# etch-a-sketch.net
KiCad netlist of a schematic drawn in EAGLE
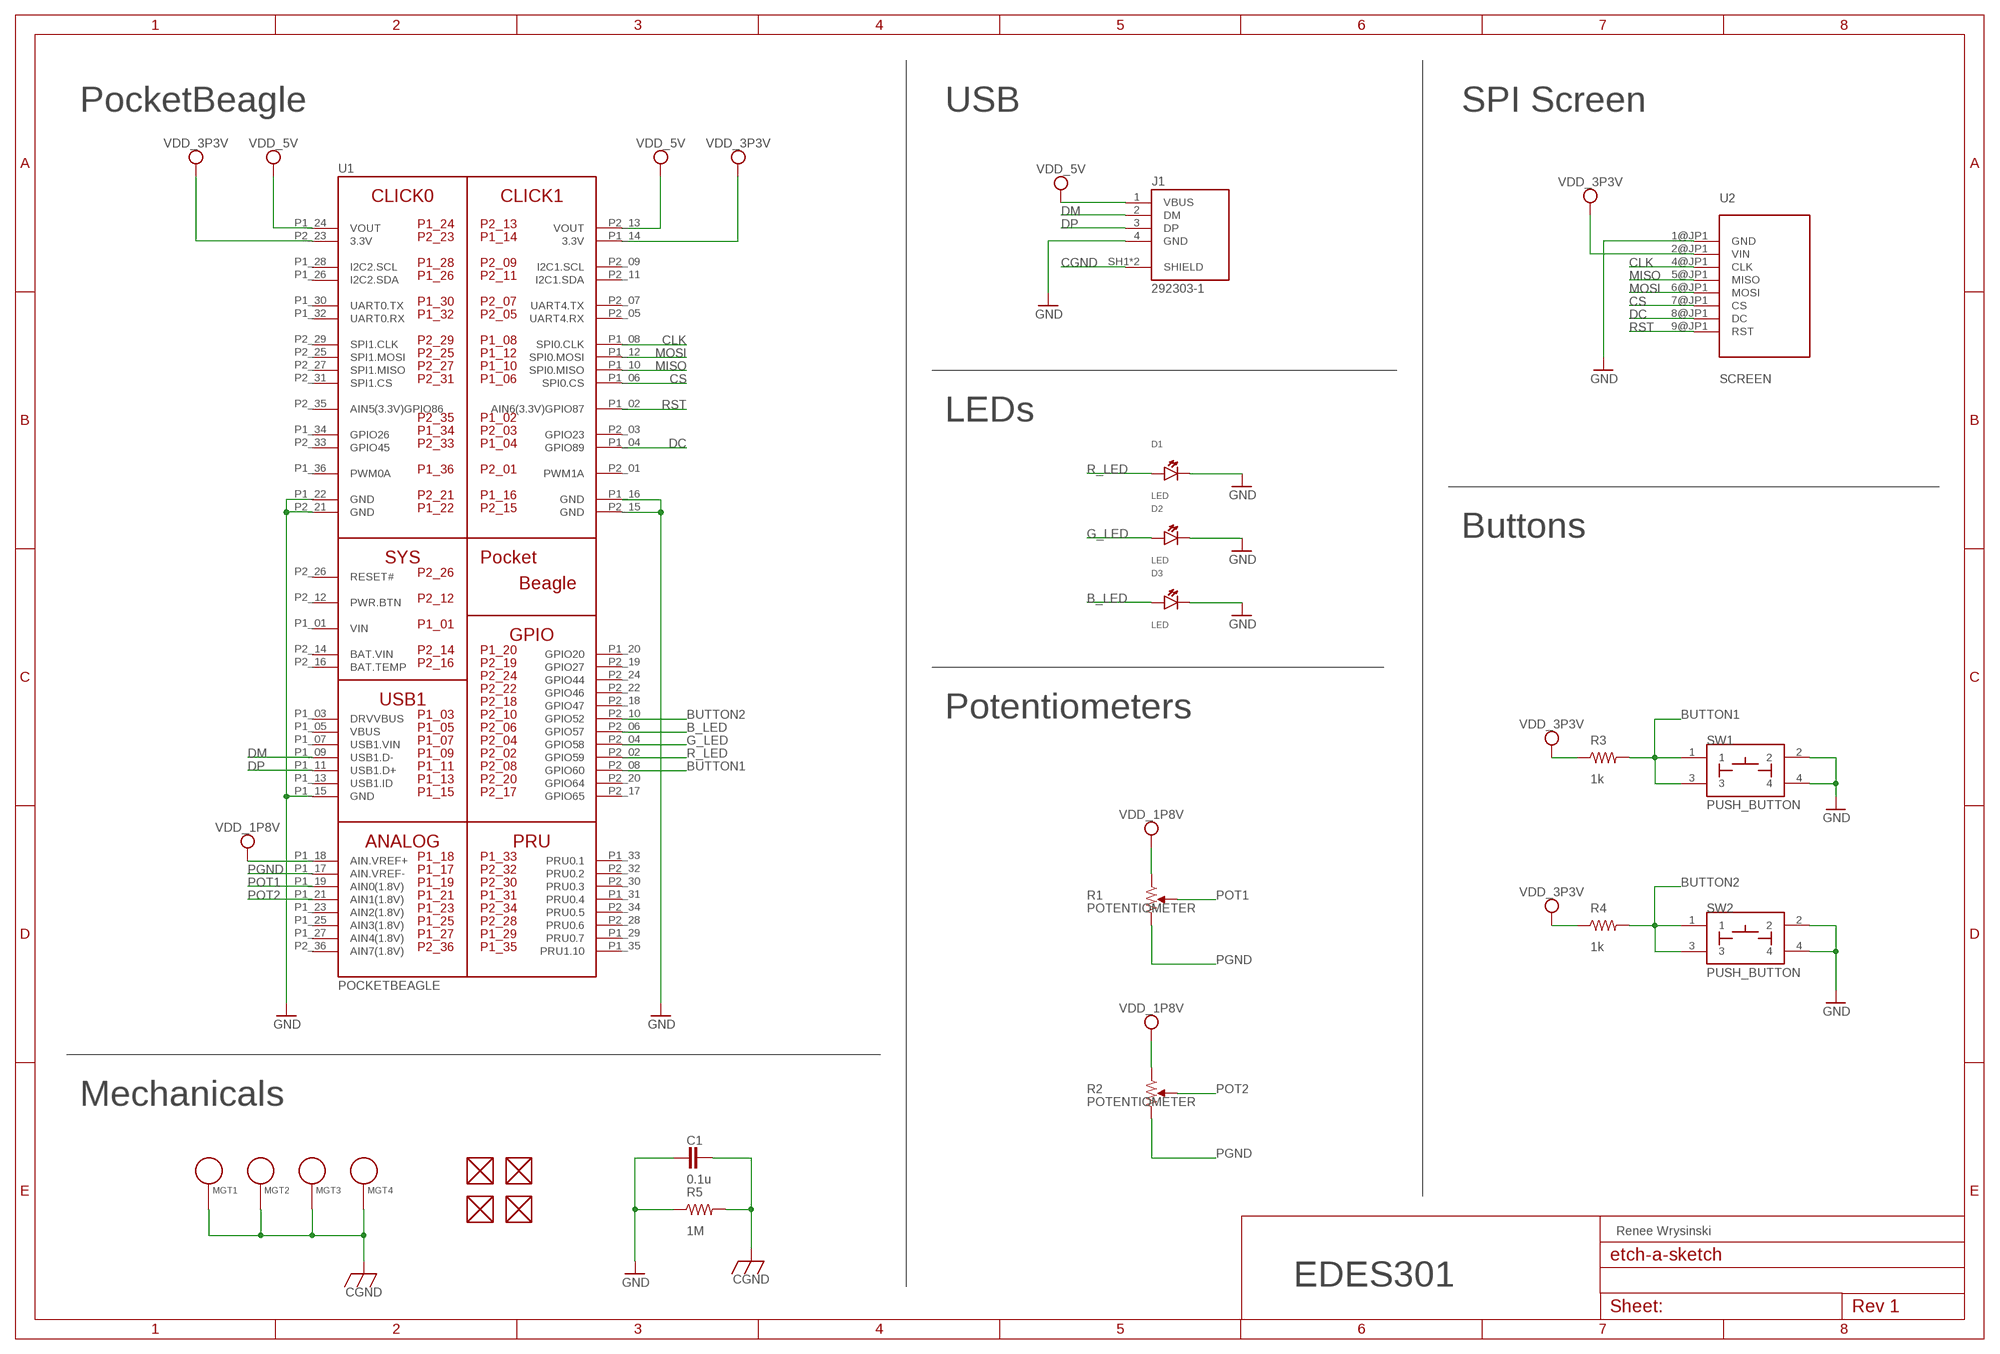
[diagram p0: schematic, sheet 1]

(export (version "E")
  (design (tool "Eeschema 10.0.6"))
  (components
    (comp (ref "C1")
      (value "0.1u")
      (footprint "eagle-import:C0603")
      (libsource (lib "eagle-import") (part "C_C0603"))
    )
    (comp (ref "D1")
      (value "LED")
      (footprint "eagle-import:EIA-STD")
      (libsource (lib "eagle-import") (part "LED"))
    )
    (comp (ref "D2")
      (value "LED")
      (footprint "eagle-import:EIA-STD")
      (libsource (lib "eagle-import") (part "LED"))
    )
    (comp (ref "D3")
      (value "LED")
      (footprint "eagle-import:EIA-STD")
      (libsource (lib "eagle-import") (part "LED"))
    )
    (comp (ref "FUD1")
      (value "FIDUCIAL")
      (footprint "eagle-import:FIDUCIAL_40MIL")
      (libsource (lib "eagle-import") (part "FIDUCIAL"))
    )
    (comp (ref "FUD2")
      (value "FIDUCIAL")
      (footprint "eagle-import:FIDUCIAL_40MIL")
      (libsource (lib "eagle-import") (part "FIDUCIAL"))
    )
    (comp (ref "FUD3")
      (value "FIDUCIAL")
      (footprint "eagle-import:FIDUCIAL_40MIL")
      (libsource (lib "eagle-import") (part "FIDUCIAL"))
    )
    (comp (ref "FUD4")
      (value "FIDUCIAL")
      (footprint "eagle-import:FIDUCIAL_40MIL")
      (libsource (lib "eagle-import") (part "FIDUCIAL"))
    )
    (comp (ref "J1")
      (value "292303-1")
      (footprint "eagle-import:TE_292303-1")
      (fields (field (name "MF") "TE Connectivity"))
      (libsource (lib "eagle-import") (part "292303-1"))
    )
    (comp (ref "MGT1")
      (value "MOUNTING_HOLE")
      (footprint "eagle-import:MOUNTING_HOLE")
      (libsource (lib "eagle-import") (part "MOUNTING_HOLE"))
    )
    (comp (ref "MGT2")
      (value "MOUNTING_HOLE")
      (footprint "eagle-import:MOUNTING_HOLE")
      (libsource (lib "eagle-import") (part "MOUNTING_HOLE"))
    )
    (comp (ref "MGT3")
      (value "MOUNTING_HOLE")
      (footprint "eagle-import:MOUNTING_HOLE")
      (libsource (lib "eagle-import") (part "MOUNTING_HOLE"))
    )
    (comp (ref "MGT4")
      (value "MOUNTING_HOLE")
      (footprint "eagle-import:MOUNTING_HOLE")
      (libsource (lib "eagle-import") (part "MOUNTING_HOLE"))
    )
    (comp (ref "R1")
      (value "POTENTIOMETER")
      (footprint "eagle-import:POT-PO90S")
      (libsource (lib "eagle-import") (part "POTENTIOMETER"))
    )
    (comp (ref "R2")
      (value "POTENTIOMETER")
      (footprint "eagle-import:POT-PO90S")
      (libsource (lib "eagle-import") (part "POTENTIOMETER"))
    )
    (comp (ref "R3")
      (value "1k")
      (footprint "eagle-import:R0603")
      (libsource (lib "eagle-import") (part "R_R0603"))
    )
    (comp (ref "R4")
      (value "1k")
      (footprint "eagle-import:R0603")
      (libsource (lib "eagle-import") (part "R_R0603"))
    )
    (comp (ref "R5")
      (value "1M")
      (footprint "eagle-import:R0603")
      (libsource (lib "eagle-import") (part "R_R0603"))
    )
    (comp (ref "SW1")
      (value "PUSH_BUTTON")
      (footprint "eagle-import:BUTTON_12.5MM")
      (libsource (lib "eagle-import") (part "PUSH_BUTTON"))
    )
    (comp (ref "SW2")
      (value "PUSH_BUTTON")
      (footprint "eagle-import:BUTTON_12.5MM")
      (libsource (lib "eagle-import") (part "PUSH_BUTTON"))
    )
    (comp (ref "U1")
      (value "POCKETBEAGLE")
      (footprint "eagle-import:POCKETBEAGLE")
      (libsource (lib "eagle-import") (part "POCKETBEAGLE"))
    )
    (comp (ref "U2")
      (value "SCREEN")
      (footprint "eagle-import:ADAFRUIT_2.8_TFT_BREAKOUT_V2")
      (libsource (lib "eagle-import") (part "ADAFRUIT_2.8_TFT_BREAKOUT_V2"))
    )
  )
  (nets
    (net (code "1") (name "/BAT.VIN") (class "Default")
      (node (ref "U1") (pin "P2_14") (pinfunction "BAT.VIN_P2_14") (pintype "power_in"))
    )
    (net (code "2") (name "/BUTTON1") (class "Default")
      (node (ref "R3") (pin "2") (pinfunction "2_2") (pintype "passive"))
      (node (ref "SW1") (pin "1") (pinfunction "1_1") (pintype "bidirectional"))
      (node (ref "SW1") (pin "3") (pinfunction "3_3") (pintype "bidirectional"))
      (node (ref "U1") (pin "P2_08") (pinfunction "GPIO60_P2_08") (pintype "bidirectional"))
    )
    (net (code "3") (name "/BUTTON2") (class "Default")
      (node (ref "R4") (pin "2") (pinfunction "2_2") (pintype "passive"))
      (node (ref "SW2") (pin "1") (pinfunction "1_1") (pintype "bidirectional"))
      (node (ref "SW2") (pin "3") (pinfunction "3_3") (pintype "bidirectional"))
      (node (ref "U1") (pin "P2_10") (pinfunction "GPIO52_P2_10") (pintype "bidirectional"))
    )
    (net (code "4") (name "/B_LED") (class "Default")
      (node (ref "D3") (pin "ANODE") (pinfunction "ANODE_ANODE") (pintype "bidirectional"))
      (node (ref "U1") (pin "P2_06") (pinfunction "GPIO57_P2_06") (pintype "bidirectional"))
    )
    (net (code "5") (name "/CLK") (class "Default")
      (node (ref "U1") (pin "P1_08") (pinfunction "SPI0.CLK_P1_08") (pintype "bidirectional"))
      (node (ref "U2") (pin "4@JP1") (pinfunction "CLK_4@JP1") (pintype "bidirectional"))
    )
    (net (code "6") (name "/CS") (class "Default")
      (node (ref "U1") (pin "P1_06") (pinfunction "SPI0.CS_P1_06") (pintype "bidirectional"))
      (node (ref "U2") (pin "7@JP1") (pinfunction "CS_7@JP1") (pintype "bidirectional"))
    )
    (net (code "7") (name "/DC") (class "Default")
      (node (ref "U1") (pin "P1_04") (pinfunction "GPIO89_P1_04") (pintype "bidirectional"))
      (node (ref "U2") (pin "8@JP1") (pinfunction "DC_8@JP1") (pintype "bidirectional"))
    )
    (net (code "8") (name "/DM") (class "Default")
      (node (ref "J1") (pin "2") (pinfunction "DM_2") (pintype "passive"))
      (node (ref "U1") (pin "P1_09") (pinfunction "USB1.D-_P1_09") (pintype "bidirectional"))
    )
    (net (code "9") (name "/DP") (class "Default")
      (node (ref "J1") (pin "3") (pinfunction "DP_3") (pintype "passive"))
      (node (ref "U1") (pin "P1_11") (pinfunction "USB1.D+_P1_11") (pintype "bidirectional"))
    )
    (net (code "10") (name "/G_LED") (class "Default")
      (node (ref "D2") (pin "ANODE") (pinfunction "ANODE_ANODE") (pintype "bidirectional"))
      (node (ref "U1") (pin "P2_04") (pinfunction "GPIO58_P2_04") (pintype "bidirectional"))
    )
    (net (code "11") (name "/MISO") (class "Default")
      (node (ref "U1") (pin "P1_10") (pinfunction "SPI0.MISO_P1_10") (pintype "bidirectional"))
      (node (ref "U2") (pin "5@JP1") (pinfunction "MISO_5@JP1") (pintype "bidirectional"))
    )
    (net (code "12") (name "/MOSI") (class "Default")
      (node (ref "U1") (pin "P1_12") (pinfunction "SPI0.MOSI_P1_12") (pintype "bidirectional"))
      (node (ref "U2") (pin "6@JP1") (pinfunction "MOSI_6@JP1") (pintype "bidirectional"))
    )
    (net (code "13") (name "/PGND") (class "Default")
      (node (ref "R1") (pin "CW") (pinfunction "CW_CW") (pintype "passive"))
      (node (ref "R2") (pin "CW") (pinfunction "CW_CW") (pintype "passive"))
      (node (ref "U1") (pin "P1_17") (pinfunction "AIN.VREF-_P1_17") (pintype "input"))
    )
    (net (code "14") (name "/POT1") (class "Default")
      (node (ref "R1") (pin "S") (pinfunction "S_S") (pintype "bidirectional"))
      (node (ref "U1") (pin "P1_19") (pinfunction "AIN0(1.8V)_P1_19") (pintype "input"))
    )
    (net (code "15") (name "/POT2") (class "Default")
      (node (ref "R2") (pin "S") (pinfunction "S_S") (pintype "bidirectional"))
      (node (ref "U1") (pin "P1_21") (pinfunction "AIN1(1.8V)_P1_21") (pintype "input"))
    )
    (net (code "16") (name "/RST") (class "Default")
      (node (ref "U1") (pin "P1_02") (pinfunction "AIN6(3.3V)GPIO87_P1_02") (pintype "bidirectional"))
      (node (ref "U2") (pin "9@JP1") (pinfunction "RST_9@JP1") (pintype "bidirectional"))
    )
    (net (code "17") (name "/R_LED") (class "Default")
      (node (ref "D1") (pin "ANODE") (pinfunction "ANODE_ANODE") (pintype "bidirectional"))
      (node (ref "U1") (pin "P2_02") (pinfunction "GPIO59_P2_02") (pintype "bidirectional"))
    )
    (net (code "18") (name "/VIN") (class "Default")
      (node (ref "U1") (pin "P1_01") (pinfunction "VIN_P1_01") (pintype "power_in"))
    )
    (net (code "19") (name "CGND") (class "Default")
      (node (ref "C1") (pin "2") (pinfunction "2_2") (pintype "passive"))
      (node (ref "J1") (pin "SH1") (pinfunction "SHIELD_SH1") (pintype "passive"))
      (node (ref "J1") (pin "SH2") (pinfunction "SHIELD_SH2") (pintype "passive"))
      (node (ref "MGT1") (pin "P$1") (pinfunction "P$1_P$1") (pintype "bidirectional"))
      (node (ref "MGT2") (pin "P$1") (pinfunction "P$1_P$1") (pintype "bidirectional"))
      (node (ref "MGT3") (pin "P$1") (pinfunction "P$1_P$1") (pintype "bidirectional"))
      (node (ref "MGT4") (pin "P$1") (pinfunction "P$1_P$1") (pintype "bidirectional"))
      (node (ref "R5") (pin "2") (pinfunction "2_2") (pintype "passive"))
    )
    (net (code "20") (name "GND") (class "Default")
      (node (ref "C1") (pin "1") (pinfunction "1_1") (pintype "passive"))
      (node (ref "D1") (pin "CATHODE") (pinfunction "CATHODE_CATHODE") (pintype "bidirectional"))
      (node (ref "D2") (pin "CATHODE") (pinfunction "CATHODE_CATHODE") (pintype "bidirectional"))
      (node (ref "D3") (pin "CATHODE") (pinfunction "CATHODE_CATHODE") (pintype "bidirectional"))
      (node (ref "J1") (pin "4") (pinfunction "GND_4") (pintype "passive"))
      (node (ref "R5") (pin "1") (pinfunction "1_1") (pintype "passive"))
      (node (ref "SW1") (pin "2") (pinfunction "2_2") (pintype "bidirectional"))
      (node (ref "SW1") (pin "4") (pinfunction "4_4") (pintype "bidirectional"))
      (node (ref "SW2") (pin "2") (pinfunction "2_2") (pintype "bidirectional"))
      (node (ref "SW2") (pin "4") (pinfunction "4_4") (pintype "bidirectional"))
      (node (ref "U1") (pin "P1_15") (pinfunction "GND_P1_15") (pintype "bidirectional"))
      (node (ref "U1") (pin "P1_16") (pinfunction "GND_P1_16") (pintype "power_in"))
      (node (ref "U1") (pin "P1_22") (pinfunction "GND_P1_22") (pintype "power_in"))
      (node (ref "U1") (pin "P2_15") (pinfunction "GND_P2_15") (pintype "power_in"))
      (node (ref "U1") (pin "P2_21") (pinfunction "GND_P2_21") (pintype "power_in"))
      (node (ref "U2") (pin "1@JP1") (pinfunction "GND_1@JP1") (pintype "bidirectional"))
    )
    (net (code "21") (name "VDD_1P8V") (class "Default")
      (node (ref "R1") (pin "CCW") (pinfunction "CCW_CCW") (pintype "passive"))
      (node (ref "R2") (pin "CCW") (pinfunction "CCW_CCW") (pintype "passive"))
      (node (ref "U1") (pin "P1_18") (pinfunction "AIN.VREF+_P1_18") (pintype "input"))
    )
    (net (code "22") (name "VDD_3P3V") (class "Default")
      (node (ref "R3") (pin "1") (pinfunction "1_1") (pintype "passive"))
      (node (ref "R4") (pin "1") (pinfunction "1_1") (pintype "passive"))
      (node (ref "U1") (pin "P1_14") (pinfunction "3.3V_P1_14") (pintype "power_in"))
      (node (ref "U1") (pin "P2_23") (pinfunction "3.3V_P2_23") (pintype "power_in"))
      (node (ref "U2") (pin "2@JP1") (pinfunction "VIN_2@JP1") (pintype "bidirectional"))
    )
    (net (code "23") (name "VDD_5V") (class "Default")
      (node (ref "J1") (pin "1") (pinfunction "VBUS_1") (pintype "passive"))
      (node (ref "U1") (pin "P1_24") (pinfunction "VOUT_P1_24") (pintype "power_in"))
      (node (ref "U1") (pin "P2_13") (pinfunction "VOUT_P2_13") (pintype "power_in"))
    )
    (net (code "24") (name "unconnected-(FUD1-PadP$1)") (class "Default")
      (node (ref "FUD1") (pin "P$1") (pinfunction "P$1_P$1") (pintype "no_connect"))
    )
    (net (code "25") (name "unconnected-(FUD2-PadP$1)") (class "Default")
      (node (ref "FUD2") (pin "P$1") (pinfunction "P$1_P$1") (pintype "no_connect"))
    )
    (net (code "26") (name "unconnected-(FUD3-PadP$1)") (class "Default")
      (node (ref "FUD3") (pin "P$1") (pinfunction "P$1_P$1") (pintype "no_connect"))
    )
    (net (code "27") (name "unconnected-(FUD4-PadP$1)") (class "Default")
      (node (ref "FUD4") (pin "P$1") (pinfunction "P$1_P$1") (pintype "no_connect"))
    )
    (net (code "28") (name "unconnected-(U1-AIN2(1.8V)-PadP1_23)") (class "Default")
      (node (ref "U1") (pin "P1_23") (pinfunction "AIN2(1.8V)_P1_23") (pintype "input"))
    )
    (net (code "29") (name "unconnected-(U1-AIN3(1.8V)-PadP1_25)") (class "Default")
      (node (ref "U1") (pin "P1_25") (pinfunction "AIN3(1.8V)_P1_25") (pintype "input"))
    )
    (net (code "30") (name "unconnected-(U1-AIN4(1.8V)-PadP1_27)") (class "Default")
      (node (ref "U1") (pin "P1_27") (pinfunction "AIN4(1.8V)_P1_27") (pintype "input"))
    )
    (net (code "31") (name "unconnected-(U1-AIN5(3.3V)GPIO86-PadP2_35)") (class "Default")
      (node (ref "U1") (pin "P2_35") (pinfunction "AIN5(3.3V)GPIO86_P2_35") (pintype "bidirectional"))
    )
    (net (code "32") (name "unconnected-(U1-AIN7(1.8V)-PadP2_36)") (class "Default")
      (node (ref "U1") (pin "P2_36") (pinfunction "AIN7(1.8V)_P2_36") (pintype "input"))
    )
    (net (code "33") (name "unconnected-(U1-BAT.TEMP-PadP2_16)") (class "Default")
      (node (ref "U1") (pin "P2_16") (pinfunction "BAT.TEMP_P2_16") (pintype "input"))
    )
    (net (code "34") (name "unconnected-(U1-DRVVBUS-PadP1_03)") (class "Default")
      (node (ref "U1") (pin "P1_03") (pinfunction "DRVVBUS_P1_03") (pintype "bidirectional"))
    )
    (net (code "35") (name "unconnected-(U1-GPIO20-PadP1_20)") (class "Default")
      (node (ref "U1") (pin "P1_20") (pinfunction "GPIO20_P1_20") (pintype "bidirectional"))
    )
    (net (code "36") (name "unconnected-(U1-GPIO23-PadP2_03)") (class "Default")
      (node (ref "U1") (pin "P2_03") (pinfunction "GPIO23_P2_03") (pintype "bidirectional"))
    )
    (net (code "37") (name "unconnected-(U1-GPIO26-PadP1_34)") (class "Default")
      (node (ref "U1") (pin "P1_34") (pinfunction "GPIO26_P1_34") (pintype "bidirectional"))
    )
    (net (code "38") (name "unconnected-(U1-GPIO27-PadP2_19)") (class "Default")
      (node (ref "U1") (pin "P2_19") (pinfunction "GPIO27_P2_19") (pintype "bidirectional"))
    )
    (net (code "39") (name "unconnected-(U1-GPIO44-PadP2_24)") (class "Default")
      (node (ref "U1") (pin "P2_24") (pinfunction "GPIO44_P2_24") (pintype "bidirectional"))
    )
    (net (code "40") (name "unconnected-(U1-GPIO45-PadP2_33)") (class "Default")
      (node (ref "U1") (pin "P2_33") (pinfunction "GPIO45_P2_33") (pintype "bidirectional"))
    )
    (net (code "41") (name "unconnected-(U1-GPIO46-PadP2_22)") (class "Default")
      (node (ref "U1") (pin "P2_22") (pinfunction "GPIO46_P2_22") (pintype "bidirectional"))
    )
    (net (code "42") (name "unconnected-(U1-GPIO47-PadP2_18)") (class "Default")
      (node (ref "U1") (pin "P2_18") (pinfunction "GPIO47_P2_18") (pintype "bidirectional"))
    )
    (net (code "43") (name "unconnected-(U1-GPIO64-PadP2_20)") (class "Default")
      (node (ref "U1") (pin "P2_20") (pinfunction "GPIO64_P2_20") (pintype "bidirectional"))
    )
    (net (code "44") (name "unconnected-(U1-GPIO65-PadP2_17)") (class "Default")
      (node (ref "U1") (pin "P2_17") (pinfunction "GPIO65_P2_17") (pintype "bidirectional"))
    )
    (net (code "45") (name "unconnected-(U1-I2C1.SCL-PadP2_09)") (class "Default")
      (node (ref "U1") (pin "P2_09") (pinfunction "I2C1.SCL_P2_09") (pintype "bidirectional"))
    )
    (net (code "46") (name "unconnected-(U1-I2C1.SDA-PadP2_11)") (class "Default")
      (node (ref "U1") (pin "P2_11") (pinfunction "I2C1.SDA_P2_11") (pintype "bidirectional"))
    )
    (net (code "47") (name "unconnected-(U1-I2C2.SCL-PadP1_28)") (class "Default")
      (node (ref "U1") (pin "P1_28") (pinfunction "I2C2.SCL_P1_28") (pintype "bidirectional"))
    )
    (net (code "48") (name "unconnected-(U1-I2C2.SDA-PadP1_26)") (class "Default")
      (node (ref "U1") (pin "P1_26") (pinfunction "I2C2.SDA_P1_26") (pintype "bidirectional"))
    )
    (net (code "49") (name "unconnected-(U1-PRU0.1-PadP1_33)") (class "Default")
      (node (ref "U1") (pin "P1_33") (pinfunction "PRU0.1_P1_33") (pintype "bidirectional"))
    )
    (net (code "50") (name "unconnected-(U1-PRU0.2-PadP2_32)") (class "Default")
      (node (ref "U1") (pin "P2_32") (pinfunction "PRU0.2_P2_32") (pintype "bidirectional"))
    )
    (net (code "51") (name "unconnected-(U1-PRU0.3-PadP2_30)") (class "Default")
      (node (ref "U1") (pin "P2_30") (pinfunction "PRU0.3_P2_30") (pintype "bidirectional"))
    )
    (net (code "52") (name "unconnected-(U1-PRU0.4-PadP1_31)") (class "Default")
      (node (ref "U1") (pin "P1_31") (pinfunction "PRU0.4_P1_31") (pintype "bidirectional"))
    )
    (net (code "53") (name "unconnected-(U1-PRU0.5-PadP2_34)") (class "Default")
      (node (ref "U1") (pin "P2_34") (pinfunction "PRU0.5_P2_34") (pintype "bidirectional"))
    )
    (net (code "54") (name "unconnected-(U1-PRU0.6-PadP2_28)") (class "Default")
      (node (ref "U1") (pin "P2_28") (pinfunction "PRU0.6_P2_28") (pintype "bidirectional"))
    )
    (net (code "55") (name "unconnected-(U1-PRU0.7-PadP1_29)") (class "Default")
      (node (ref "U1") (pin "P1_29") (pinfunction "PRU0.7_P1_29") (pintype "bidirectional"))
    )
    (net (code "56") (name "unconnected-(U1-PRU1.10-PadP1_35)") (class "Default")
      (node (ref "U1") (pin "P1_35") (pinfunction "PRU1.10_P1_35") (pintype "bidirectional"))
    )
    (net (code "57") (name "unconnected-(U1-PWM0A-PadP1_36)") (class "Default")
      (node (ref "U1") (pin "P1_36") (pinfunction "PWM0A_P1_36") (pintype "bidirectional"))
    )
    (net (code "58") (name "unconnected-(U1-PWM1A-PadP2_01)") (class "Default")
      (node (ref "U1") (pin "P2_01") (pinfunction "PWM1A_P2_01") (pintype "bidirectional"))
    )
    (net (code "59") (name "unconnected-(U1-PWR.BTN-PadP2_12)") (class "Default")
      (node (ref "U1") (pin "P2_12") (pinfunction "PWR.BTN_P2_12") (pintype "input"))
    )
    (net (code "60") (name "unconnected-(U1-RESET#-PadP2_26)") (class "Default")
      (node (ref "U1") (pin "P2_26") (pinfunction "RESET#_P2_26") (pintype "input"))
    )
    (net (code "61") (name "unconnected-(U1-SPI1.CLK-PadP2_29)") (class "Default")
      (node (ref "U1") (pin "P2_29") (pinfunction "SPI1.CLK_P2_29") (pintype "bidirectional"))
    )
    (net (code "62") (name "unconnected-(U1-SPI1.CS-PadP2_31)") (class "Default")
      (node (ref "U1") (pin "P2_31") (pinfunction "SPI1.CS_P2_31") (pintype "bidirectional"))
    )
    (net (code "63") (name "unconnected-(U1-SPI1.MISO-PadP2_27)") (class "Default")
      (node (ref "U1") (pin "P2_27") (pinfunction "SPI1.MISO_P2_27") (pintype "bidirectional"))
    )
    (net (code "64") (name "unconnected-(U1-SPI1.MOSI-PadP2_25)") (class "Default")
      (node (ref "U1") (pin "P2_25") (pinfunction "SPI1.MOSI_P2_25") (pintype "bidirectional"))
    )
    (net (code "65") (name "unconnected-(U1-UART0.RX-PadP1_32)") (class "Default")
      (node (ref "U1") (pin "P1_32") (pinfunction "UART0.RX_P1_32") (pintype "bidirectional"))
    )
    (net (code "66") (name "unconnected-(U1-UART0.TX-PadP1_30)") (class "Default")
      (node (ref "U1") (pin "P1_30") (pinfunction "UART0.TX_P1_30") (pintype "bidirectional"))
    )
    (net (code "67") (name "unconnected-(U1-UART4.RX-PadP2_05)") (class "Default")
      (node (ref "U1") (pin "P2_05") (pinfunction "UART4.RX_P2_05") (pintype "bidirectional"))
    )
    (net (code "68") (name "unconnected-(U1-UART4.TX-PadP2_07)") (class "Default")
      (node (ref "U1") (pin "P2_07") (pinfunction "UART4.TX_P2_07") (pintype "bidirectional"))
    )
    (net (code "69") (name "unconnected-(U1-USB1.ID-PadP1_13)") (class "Default")
      (node (ref "U1") (pin "P1_13") (pinfunction "USB1.ID_P1_13") (pintype "bidirectional"))
    )
    (net (code "70") (name "unconnected-(U1-USB1.VIN-PadP1_07)") (class "Default")
      (node (ref "U1") (pin "P1_07") (pinfunction "USB1.VIN_P1_07") (pintype "bidirectional"))
    )
    (net (code "71") (name "unconnected-(U1-VBUS-PadP1_05)") (class "Default")
      (node (ref "U1") (pin "P1_05") (pinfunction "VBUS_P1_05") (pintype "bidirectional"))
    )
  )
)
